# bma-001.net
KiCad netlist of a schematic drawn in EAGLE
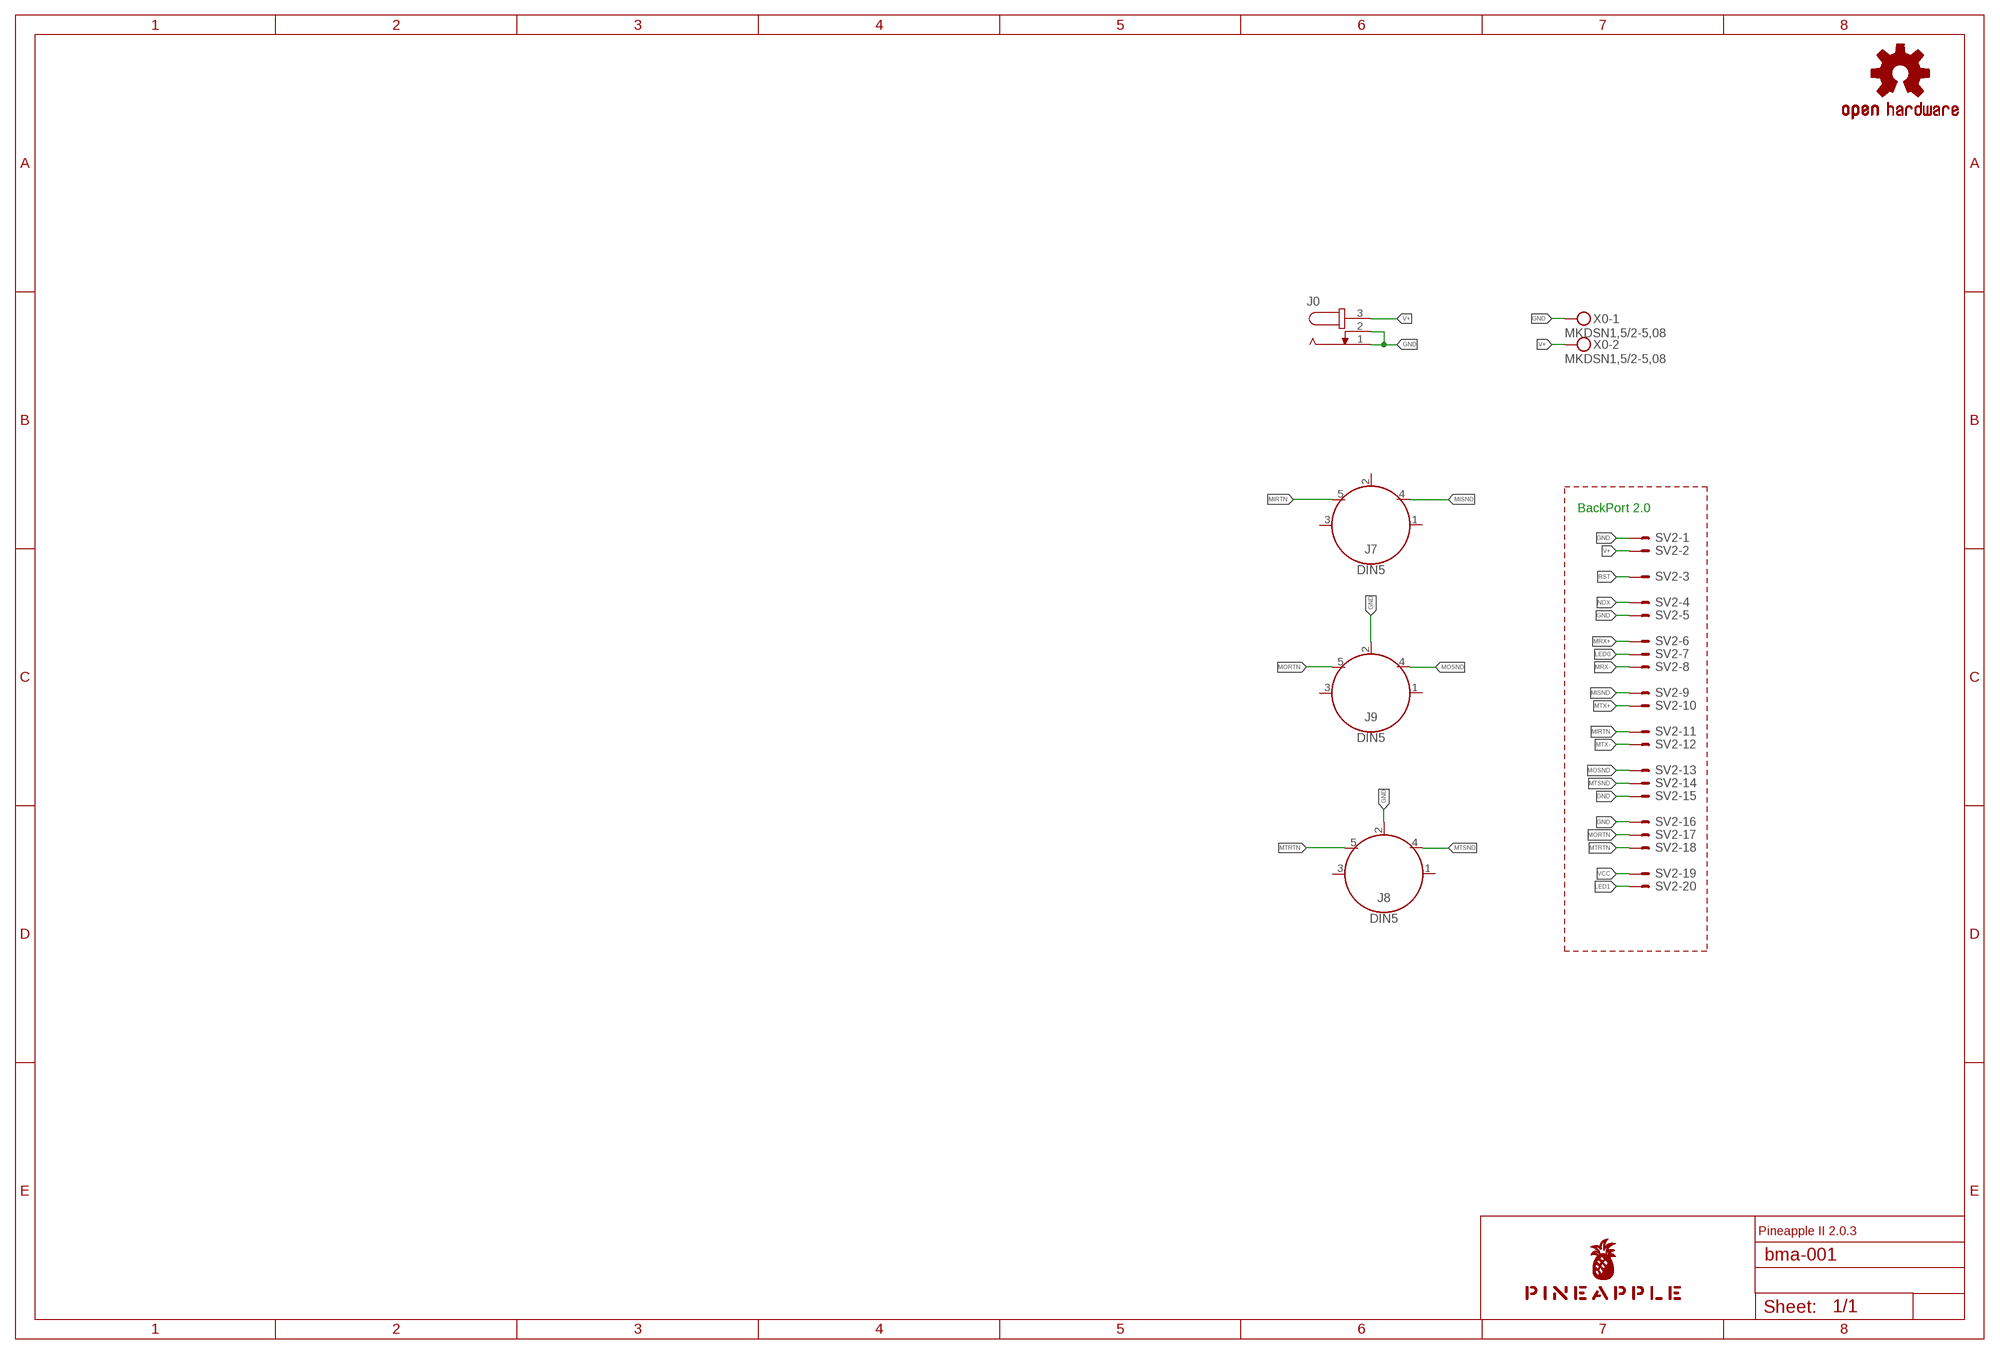
[diagram p0: schematic, sheet 1]

(export (version "E")
  (design (tool "Eeschema 10.0.6"))
  (components
    (comp (ref "J0")
      (value "JACK-PLUG0")
      (footprint "eagle-import:SPC4077")
      (libsource (lib "eagle-import") (part "JACK-PLUG0"))
    )
    (comp (ref "J7")
      (value "DIN5")
      (footprint "eagle-import:DIN5-RA-PTH")
      (libsource (lib "eagle-import") (part "DIN5"))
    )
    (comp (ref "J8")
      (value "DIN5")
      (footprint "eagle-import:DIN5-RA-PTH")
      (libsource (lib "eagle-import") (part "DIN5"))
    )
    (comp (ref "J9")
      (value "DIN5")
      (footprint "eagle-import:DIN5-RA-PTH")
      (libsource (lib "eagle-import") (part "DIN5"))
    )
    (comp (ref "LOGO1")
      (value "OSHW-LOGOS-COPPER")
      (footprint "eagle-import:OSHW-LOGO-S_COPPER")
      (libsource (lib "eagle-import") (part "OSHW-LOGOS-COPPER"))
    )
    (comp (ref "SV2")
      (value "ML20LE")
      (footprint "eagle-import:ML20L")
      (libsource (lib "eagle-import") (part "ML20LE"))
    )
    (comp (ref "U$1")
      (value "PINEAPPLE450_SILK")
      (footprint "eagle-import:PINEAPPLE450_SILK")
      (libsource (lib "eagle-import") (part "PINEAPPLE450_SILK"))
    )
    (comp (ref "X0")
      (value "MKDSN1,5/2-5,08")
      (footprint "eagle-import:MKDSN1,5_2-5,08")
      (libsource (lib "eagle-import") (part "MKDSN1,5/2-5,08"))
    )
  )
  (nets
    (net (code "1") (name "GND") (class "Default")
      (node (ref "J0") (pin "1") (pinfunction "1_1") (pintype "passive"))
      (node (ref "J0") (pin "2") (pinfunction "2_2") (pintype "passive"))
      (node (ref "J8") (pin "2") (pinfunction "2_2") (pintype "bidirectional"))
      (node (ref "J9") (pin "2") (pinfunction "2_2") (pintype "bidirectional"))
      (node (ref "SV2") (pin "1") (pinfunction "S_1") (pintype "passive"))
      (node (ref "SV2") (pin "15") (pinfunction "S_15") (pintype "passive"))
      (node (ref "SV2") (pin "16") (pinfunction "S_16") (pintype "passive"))
      (node (ref "SV2") (pin "5") (pinfunction "S_5") (pintype "passive"))
      (node (ref "X0") (pin "1") (pinfunction "KL_1") (pintype "passive"))
    )
    (net (code "2") (name "LED0") (class "Default")
      (node (ref "SV2") (pin "7") (pinfunction "S_7") (pintype "passive"))
    )
    (net (code "3") (name "LED1") (class "Default")
      (node (ref "SV2") (pin "20") (pinfunction "S_20") (pintype "passive"))
    )
    (net (code "4") (name "MIRTN") (class "Default")
      (node (ref "J7") (pin "5") (pinfunction "5_5") (pintype "bidirectional"))
      (node (ref "SV2") (pin "11") (pinfunction "S_11") (pintype "passive"))
    )
    (net (code "5") (name "MISND") (class "Default")
      (node (ref "J7") (pin "4") (pinfunction "4_4") (pintype "bidirectional"))
      (node (ref "SV2") (pin "9") (pinfunction "S_9") (pintype "passive"))
    )
    (net (code "6") (name "MORTN") (class "Default")
      (node (ref "J9") (pin "5") (pinfunction "5_5") (pintype "bidirectional"))
      (node (ref "SV2") (pin "17") (pinfunction "S_17") (pintype "passive"))
    )
    (net (code "7") (name "MOSND") (class "Default")
      (node (ref "J9") (pin "4") (pinfunction "4_4") (pintype "bidirectional"))
      (node (ref "SV2") (pin "13") (pinfunction "S_13") (pintype "passive"))
    )
    (net (code "8") (name "MRX+") (class "Default")
      (node (ref "SV2") (pin "6") (pinfunction "S_6") (pintype "passive"))
    )
    (net (code "9") (name "MRX-") (class "Default")
      (node (ref "SV2") (pin "8") (pinfunction "S_8") (pintype "passive"))
    )
    (net (code "10") (name "MTRTN") (class "Default")
      (node (ref "J8") (pin "5") (pinfunction "5_5") (pintype "bidirectional"))
      (node (ref "SV2") (pin "18") (pinfunction "S_18") (pintype "passive"))
    )
    (net (code "11") (name "MTSND") (class "Default")
      (node (ref "J8") (pin "4") (pinfunction "4_4") (pintype "bidirectional"))
      (node (ref "SV2") (pin "14") (pinfunction "S_14") (pintype "passive"))
    )
    (net (code "12") (name "MTX+") (class "Default")
      (node (ref "SV2") (pin "10") (pinfunction "S_10") (pintype "passive"))
    )
    (net (code "13") (name "MTX-") (class "Default")
      (node (ref "SV2") (pin "12") (pinfunction "S_12") (pintype "passive"))
    )
    (net (code "14") (name "NDX") (class "Default")
      (node (ref "SV2") (pin "4") (pinfunction "S_4") (pintype "passive"))
    )
    (net (code "15") (name "RST") (class "Default")
      (node (ref "SV2") (pin "3") (pinfunction "S_3") (pintype "passive"))
    )
    (net (code "16") (name "V+") (class "Default")
      (node (ref "J0") (pin "3") (pinfunction "3_3") (pintype "passive"))
      (node (ref "SV2") (pin "2") (pinfunction "S_2") (pintype "passive"))
      (node (ref "X0") (pin "2") (pinfunction "KL_2") (pintype "passive"))
    )
    (net (code "17") (name "VCC") (class "Default")
      (node (ref "SV2") (pin "19") (pinfunction "S_19") (pintype "passive"))
    )
    (net (code "18") (name "unconnected-(J7-Pad1)") (class "Default")
      (node (ref "J7") (pin "1") (pinfunction "1_1") (pintype "bidirectional"))
    )
    (net (code "19") (name "unconnected-(J7-Pad2)") (class "Default")
      (node (ref "J7") (pin "2") (pinfunction "2_2") (pintype "bidirectional"))
    )
    (net (code "20") (name "unconnected-(J7-Pad3)") (class "Default")
      (node (ref "J7") (pin "3") (pinfunction "3_3") (pintype "bidirectional"))
    )
    (net (code "21") (name "unconnected-(J8-Pad1)") (class "Default")
      (node (ref "J8") (pin "1") (pinfunction "1_1") (pintype "bidirectional"))
    )
    (net (code "22") (name "unconnected-(J8-Pad3)") (class "Default")
      (node (ref "J8") (pin "3") (pinfunction "3_3") (pintype "bidirectional"))
    )
    (net (code "23") (name "unconnected-(J9-Pad1)") (class "Default")
      (node (ref "J9") (pin "1") (pinfunction "1_1") (pintype "bidirectional"))
    )
    (net (code "24") (name "unconnected-(J9-Pad3)") (class "Default")
      (node (ref "J9") (pin "3") (pinfunction "3_3") (pintype "bidirectional"))
    )
  )
)
